# OpenSoundAnalog.net
KiCad netlist of a schematic drawn in EAGLE
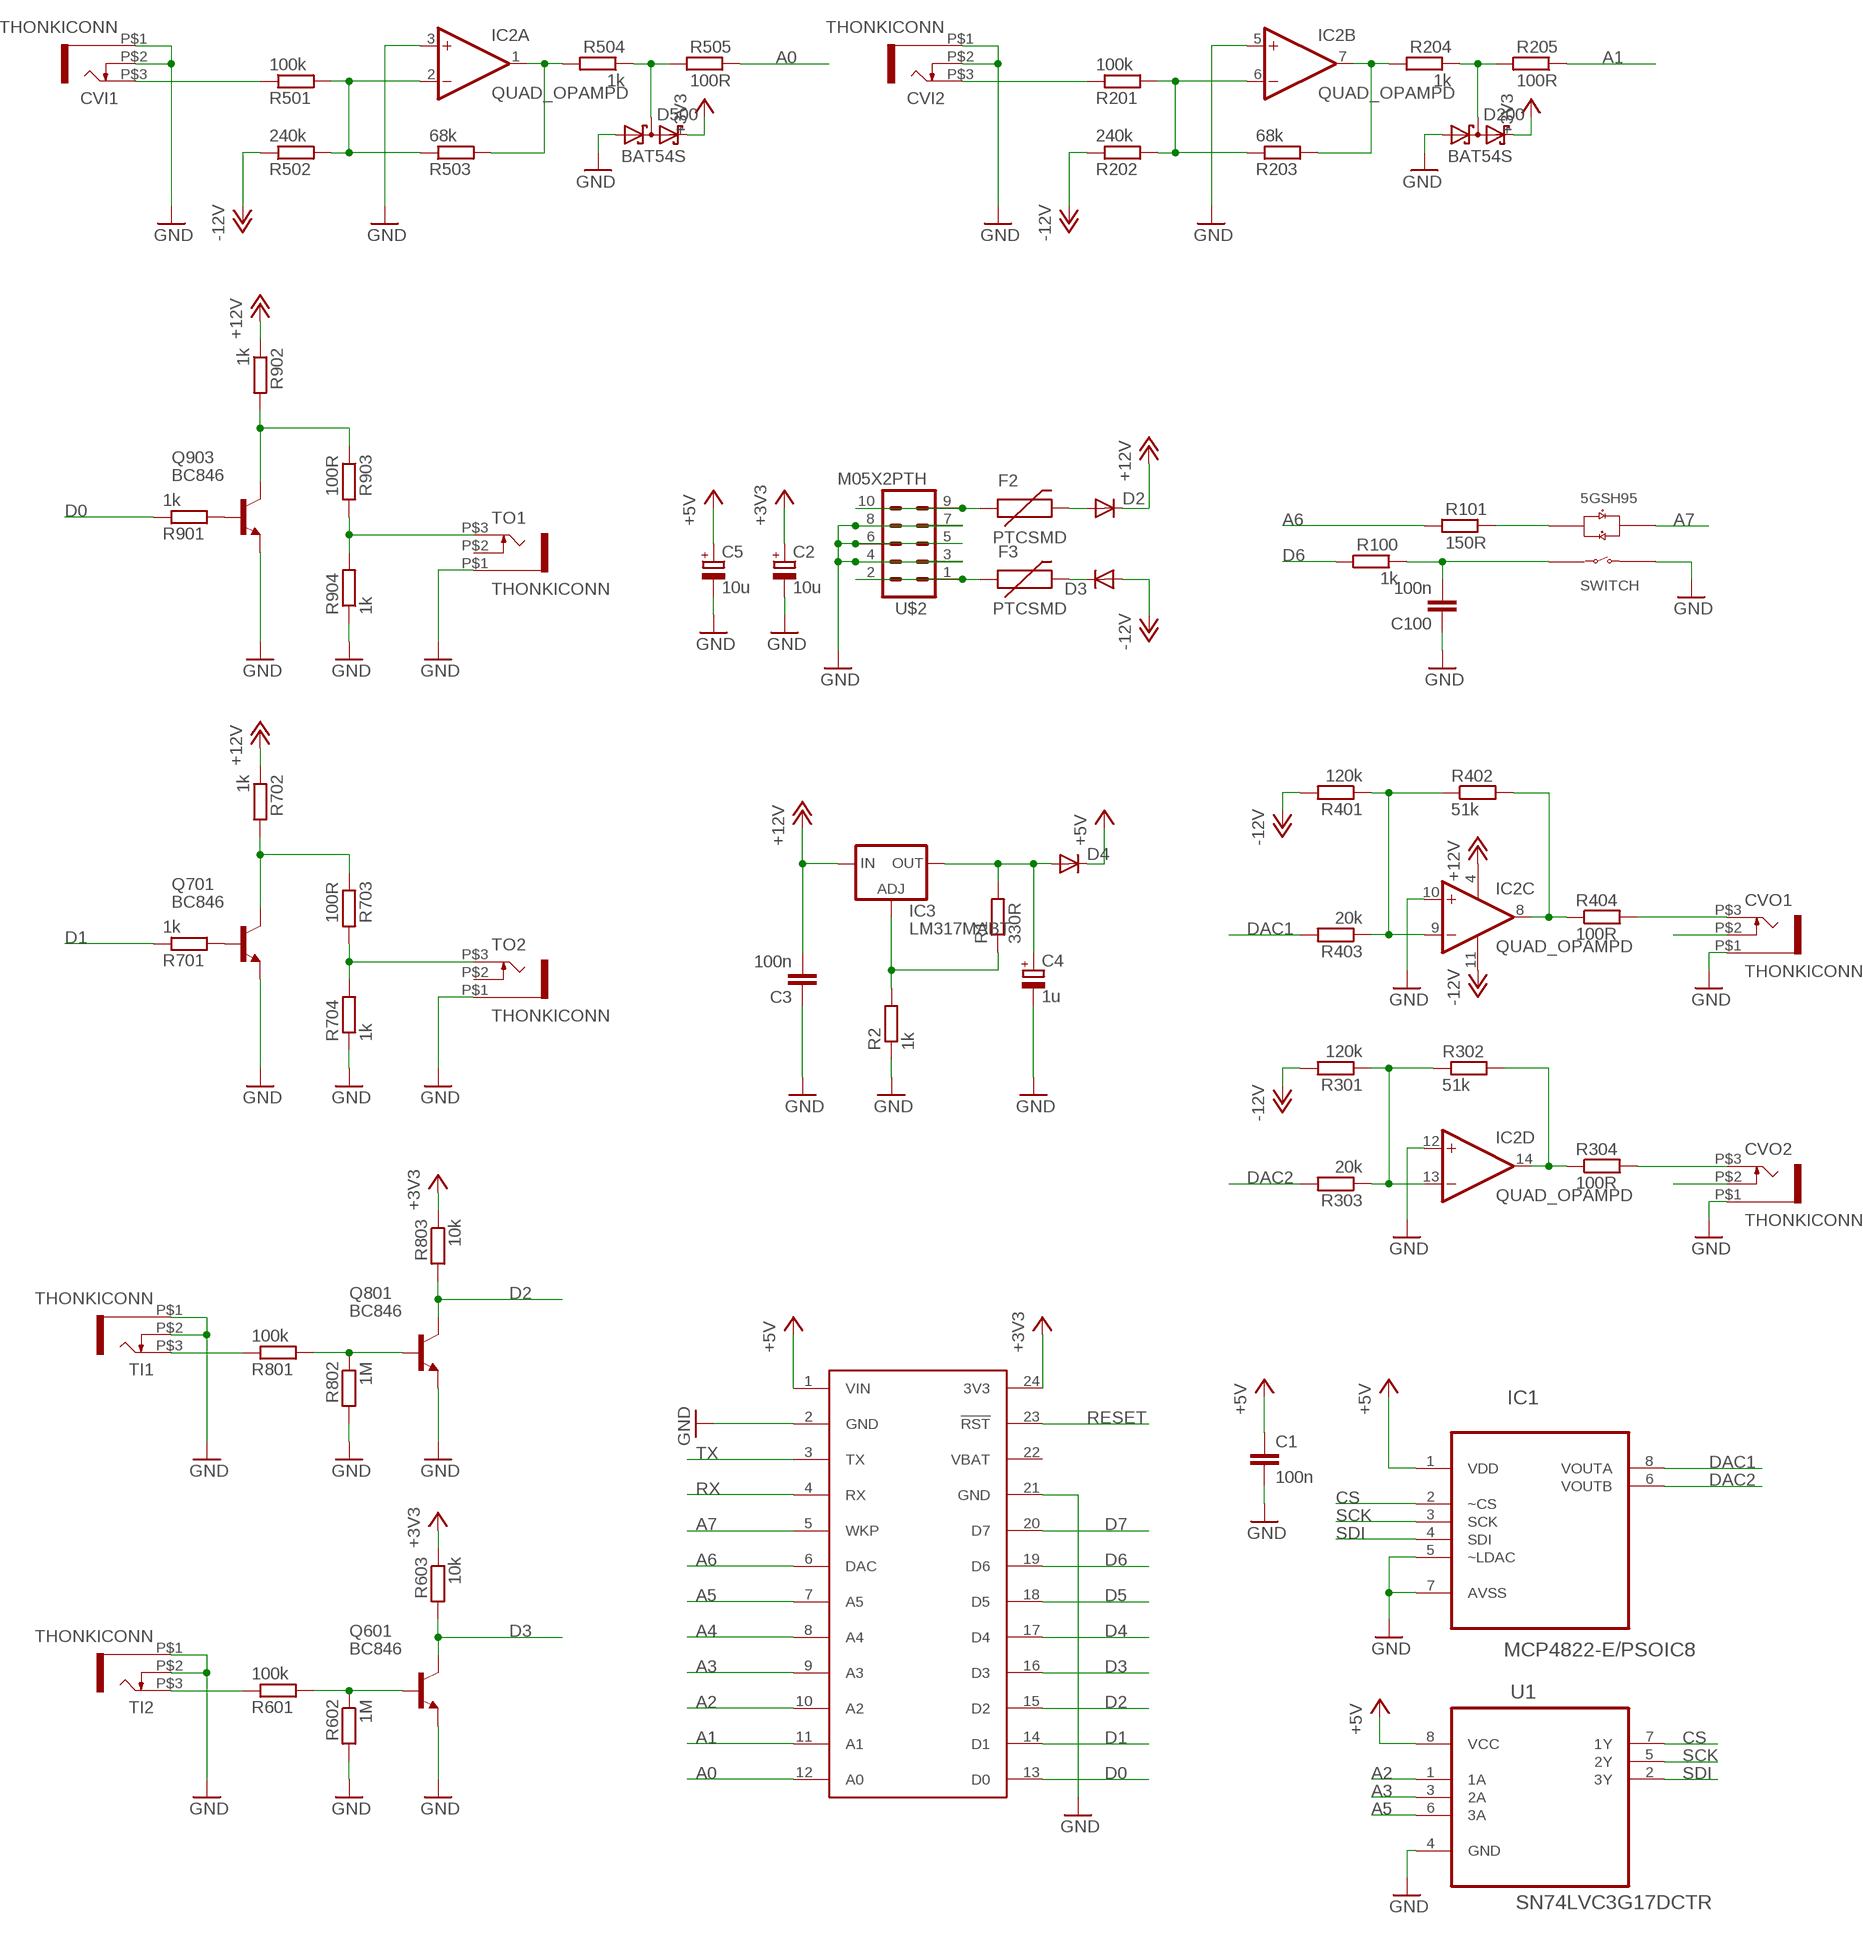
[diagram p0: schematic, sheet 1]

(export (version "E")
  (design (tool "Eeschema 10.0.6"))
  (components
    (comp (ref "C1")
      (value "100n")
      (footprint "eagle-import:C0603")
      (libsource (lib "eagle-import") (part "resistor_C-EUC0603"))
    )
    (comp (ref "C2")
      (value "10u")
      (footprint "eagle-import:SANYO-OSCON_SMD_A5")
      (libsource (lib "eagle-import") (part "CPOL-EUSANYO_SMD_A5"))
    )
    (comp (ref "C3")
      (value "100n")
      (footprint "eagle-import:C0603")
      (libsource (lib "eagle-import") (part "C-EUC0603"))
    )
    (comp (ref "C4")
      (value "1u")
      (footprint "eagle-import:SANYO-OSCON_SMD_A5")
      (libsource (lib "eagle-import") (part "CPOL-EUSANYO_SMD_A5"))
    )
    (comp (ref "C5")
      (value "10u")
      (footprint "eagle-import:SANYO-OSCON_SMD_A5")
      (libsource (lib "eagle-import") (part "CPOL-EUSANYO_SMD_A5"))
    )
    (comp (ref "C100")
      (value "100n")
      (footprint "eagle-import:C0603")
      (libsource (lib "eagle-import") (part "C-EUC0603"))
    )
    (comp (ref "CVI1")
      (value "THONKICONN")
      (footprint "eagle-import:THONKICONN")
      (libsource (lib "eagle-import") (part "THONKICONN"))
    )
    (comp (ref "CVI2")
      (value "THONKICONN")
      (footprint "eagle-import:THONKICONN")
      (libsource (lib "eagle-import") (part "THONKICONN"))
    )
    (comp (ref "CVO1")
      (value "THONKICONN")
      (footprint "eagle-import:THONKICONN")
      (libsource (lib "eagle-import") (part "THONKICONN"))
    )
    (comp (ref "CVO2")
      (value "THONKICONN")
      (footprint "eagle-import:THONKICONN")
      (libsource (lib "eagle-import") (part "THONKICONN"))
    )
    (comp (ref "D2")
      (value "DIODESMA")
      (footprint "eagle-import:SMA-DIODE")
      (libsource (lib "eagle-import") (part "DIODESMA"))
    )
    (comp (ref "D3")
      (value "DIODESMA")
      (footprint "eagle-import:SMA-DIODE")
      (libsource (lib "eagle-import") (part "DIODESMA"))
    )
    (comp (ref "D4")
      (value "DIODESMA")
      (footprint "eagle-import:SMA-DIODE")
      (libsource (lib "eagle-import") (part "DIODESMA"))
    )
    (comp (ref "D200")
      (value "BAT54S")
      (footprint "eagle-import:SOT23")
      (libsource (lib "eagle-import") (part "BAT54S"))
    )
    (comp (ref "D500")
      (value "BAT54S")
      (footprint "eagle-import:SOT23")
      (libsource (lib "eagle-import") (part "BAT54S"))
    )
    (comp (ref "F2")
      (value "PTCSMD")
      (footprint "eagle-import:PTC-1206")
      (libsource (lib "eagle-import") (part "PTCSMD"))
    )
    (comp (ref "F3")
      (value "PTCSMD")
      (footprint "eagle-import:PTC-1206")
      (libsource (lib "eagle-import") (part "PTCSMD"))
    )
    (comp (ref "IC1")
      (value "MCP4822-E/PSOIC8")
      (footprint "eagle-import:SOIC8")
      (libsource (lib "eagle-import") (part "MCP4822-E/PSOIC8"))
    )
    (comp (ref "IC2")
      (value "QUAD_OPAMPD")
      (footprint "eagle-import:SO14")
      (libsource (lib "eagle-import") (part "QUAD_OPAMPD"))
    )
    (comp (ref "IC3")
      (value "LM317MABT")
      (footprint "eagle-import:TO220L1")
      (libsource (lib "eagle-import") (part "LM317?MABT"))
    )
    (comp (ref "Q601")
      (value "BC846")
      (footprint "eagle-import:SOT23")
      (libsource (lib "eagle-import") (part "BC846"))
    )
    (comp (ref "Q701")
      (value "BC846")
      (footprint "eagle-import:SOT23")
      (libsource (lib "eagle-import") (part "BC846"))
    )
    (comp (ref "Q801")
      (value "BC846")
      (footprint "eagle-import:SOT23")
      (libsource (lib "eagle-import") (part "BC846"))
    )
    (comp (ref "Q903")
      (value "BC846")
      (footprint "eagle-import:SOT23")
      (libsource (lib "eagle-import") (part "BC846"))
    )
    (comp (ref "R1")
      (value "330R")
      (footprint "eagle-import:0603")
      (libsource (lib "eagle-import") (part "R-EU_0603"))
    )
    (comp (ref "R2")
      (value "1k")
      (footprint "eagle-import:0603")
      (libsource (lib "eagle-import") (part "R-EU_0603"))
    )
    (comp (ref "R100")
      (value "1k")
      (footprint "eagle-import:0603")
      (libsource (lib "eagle-import") (part "R-EU_0603"))
    )
    (comp (ref "R101")
      (value "150R")
      (footprint "eagle-import:0603")
      (libsource (lib "eagle-import") (part "R-EU_0603"))
    )
    (comp (ref "R201")
      (value "100k")
      (footprint "eagle-import:0603")
      (libsource (lib "eagle-import") (part "R-EU_0603"))
    )
    (comp (ref "R202")
      (value "240k")
      (footprint "eagle-import:0603")
      (libsource (lib "eagle-import") (part "R-EU_0603"))
    )
    (comp (ref "R203")
      (value "68k")
      (footprint "eagle-import:0603")
      (libsource (lib "eagle-import") (part "R-EU_0603"))
    )
    (comp (ref "R204")
      (value "1k")
      (footprint "eagle-import:0603")
      (libsource (lib "eagle-import") (part "R-EU_0603"))
    )
    (comp (ref "R205")
      (value "100R")
      (footprint "eagle-import:0603")
      (libsource (lib "eagle-import") (part "R-EU_0603"))
    )
    (comp (ref "R301")
      (value "120k")
      (footprint "eagle-import:0603")
      (libsource (lib "eagle-import") (part "R-EU_0603"))
    )
    (comp (ref "R302")
      (value "51k")
      (footprint "eagle-import:0603")
      (libsource (lib "eagle-import") (part "R-EU_0603"))
    )
    (comp (ref "R303")
      (value "20k")
      (footprint "eagle-import:0603")
      (libsource (lib "eagle-import") (part "R-EU_0603"))
    )
    (comp (ref "R304")
      (value "100R")
      (footprint "eagle-import:0603")
      (libsource (lib "eagle-import") (part "R-EU_0603"))
    )
    (comp (ref "R401")
      (value "120k")
      (footprint "eagle-import:0603")
      (libsource (lib "eagle-import") (part "R-EU_0603"))
    )
    (comp (ref "R402")
      (value "51k")
      (footprint "eagle-import:0603")
      (libsource (lib "eagle-import") (part "R-EU_0603"))
    )
    (comp (ref "R403")
      (value "20k")
      (footprint "eagle-import:0603")
      (libsource (lib "eagle-import") (part "R-EU_0603"))
    )
    (comp (ref "R404")
      (value "100R")
      (footprint "eagle-import:0603")
      (libsource (lib "eagle-import") (part "R-EU_0603"))
    )
    (comp (ref "R501")
      (value "100k")
      (footprint "eagle-import:0603")
      (libsource (lib "eagle-import") (part "R-EU_0603"))
    )
    (comp (ref "R502")
      (value "240k")
      (footprint "eagle-import:0603")
      (libsource (lib "eagle-import") (part "R-EU_0603"))
    )
    (comp (ref "R503")
      (value "68k")
      (footprint "eagle-import:0603")
      (libsource (lib "eagle-import") (part "R-EU_0603"))
    )
    (comp (ref "R504")
      (value "1k")
      (footprint "eagle-import:0603")
      (libsource (lib "eagle-import") (part "R-EU_0603"))
    )
    (comp (ref "R505")
      (value "100R")
      (footprint "eagle-import:0603")
      (libsource (lib "eagle-import") (part "R-EU_0603"))
    )
    (comp (ref "R601")
      (value "100k")
      (footprint "eagle-import:0603")
      (libsource (lib "eagle-import") (part "R-EU_0603"))
    )
    (comp (ref "R602")
      (value "1M")
      (footprint "eagle-import:0603")
      (libsource (lib "eagle-import") (part "R-EU_0603"))
    )
    (comp (ref "R603")
      (value "10k")
      (footprint "eagle-import:0603")
      (libsource (lib "eagle-import") (part "R-EU_0603"))
    )
    (comp (ref "R701")
      (value "1k")
      (footprint "eagle-import:0603")
      (libsource (lib "eagle-import") (part "R-EU_0603"))
    )
    (comp (ref "R702")
      (value "1k")
      (footprint "eagle-import:0603")
      (libsource (lib "eagle-import") (part "R-EU_0603"))
    )
    (comp (ref "R703")
      (value "100R")
      (footprint "eagle-import:0603")
      (libsource (lib "eagle-import") (part "R-EU_0603"))
    )
    (comp (ref "R704")
      (value "1k")
      (footprint "eagle-import:0603")
      (libsource (lib "eagle-import") (part "R-EU_0603"))
    )
    (comp (ref "R801")
      (value "100k")
      (footprint "eagle-import:0603")
      (libsource (lib "eagle-import") (part "R-EU_0603"))
    )
    (comp (ref "R802")
      (value "1M")
      (footprint "eagle-import:0603")
      (libsource (lib "eagle-import") (part "R-EU_0603"))
    )
    (comp (ref "R803")
      (value "10k")
      (footprint "eagle-import:0603")
      (libsource (lib "eagle-import") (part "R-EU_0603"))
    )
    (comp (ref "R901")
      (value "1k")
      (footprint "eagle-import:0603")
      (libsource (lib "eagle-import") (part "R-EU_0603"))
    )
    (comp (ref "R902")
      (value "1k")
      (footprint "eagle-import:0603")
      (libsource (lib "eagle-import") (part "R-EU_0603"))
    )
    (comp (ref "R903")
      (value "100R")
      (footprint "eagle-import:0603")
      (libsource (lib "eagle-import") (part "R-EU_0603"))
    )
    (comp (ref "R904")
      (value "1k")
      (footprint "eagle-import:0603")
      (libsource (lib "eagle-import") (part "R-EU_0603"))
    )
    (comp (ref "SPARK")
      (value "SPARK_CORE")
      (footprint "eagle-import:SPARK_CORE")
      (libsource (lib "eagle-import") (part "SPARK_CORECORE"))
    )
    (comp (ref "TI1")
      (value "THONKICONN")
      (footprint "eagle-import:THONKICONN")
      (libsource (lib "eagle-import") (part "THONKICONN"))
    )
    (comp (ref "TI2")
      (value "THONKICONN")
      (footprint "eagle-import:THONKICONN")
      (libsource (lib "eagle-import") (part "THONKICONN"))
    )
    (comp (ref "TO1")
      (value "THONKICONN")
      (footprint "eagle-import:THONKICONN")
      (libsource (lib "eagle-import") (part "THONKICONN"))
    )
    (comp (ref "TO2")
      (value "THONKICONN")
      (footprint "eagle-import:THONKICONN")
      (libsource (lib "eagle-import") (part "THONKICONN"))
    )
    (comp (ref "U$1")
      (value "5GTH9")
      (footprint "eagle-import:5GTH9")
      (libsource (lib "eagle-import") (part "5GTH9"))
    )
    (comp (ref "U$2")
      (value "M05X2PTH")
      (footprint "eagle-import:AVR_ICSP")
      (libsource (lib "eagle-import") (part "M05X2PTH"))
    )
    (comp (ref "U1")
      (value "SN74LVC3G17DCTR")
      (footprint "eagle-import:SOP65P400X130-8N")
      (libsource (lib "eagle-import") (part "SN74LVC3G17DCTR"))
    )
  )
  (nets
    (net (code "1") (name "+3V3") (class "Default")
      (node (ref "C2") (pin "+") (pinfunction "+_+") (pintype "passive"))
      (node (ref "D200") (pin "2") (pinfunction "C2_2") (pintype "passive"))
      (node (ref "D500") (pin "2") (pinfunction "C2_2") (pintype "passive"))
      (node (ref "R603") (pin "1") (pinfunction "1_1") (pintype "passive"))
      (node (ref "R803") (pin "1") (pinfunction "1_1") (pintype "passive"))
      (node (ref "SPARK") (pin "24") (pinfunction "3V3_24") (pintype "power_in"))
    )
    (net (code "2") (name "+5V") (class "Default")
      (node (ref "C1") (pin "1") (pinfunction "1_1") (pintype "passive"))
      (node (ref "C5") (pin "+") (pinfunction "+_+") (pintype "passive"))
      (node (ref "D4") (pin "C") (pinfunction "C_C") (pintype "passive"))
      (node (ref "IC1") (pin "1") (pinfunction "VDD_1") (pintype "power_in"))
      (node (ref "SPARK") (pin "1") (pinfunction "VIN_1") (pintype "power_in"))
      (node (ref "U1") (pin "8") (pinfunction "VCC_8") (pintype "power_in"))
    )
    (net (code "3") (name "+12V") (class "Default")
      (node (ref "C3") (pin "2") (pinfunction "2_2") (pintype "passive"))
      (node (ref "D2") (pin "C") (pinfunction "C_C") (pintype "passive"))
      (node (ref "IC2") (pin "4") (pinfunction "V+_4") (pintype "power_in"))
      (node (ref "IC3") (pin "3") (pinfunction "IN_3") (pintype "input"))
      (node (ref "R702") (pin "1") (pinfunction "1_1") (pintype "passive"))
      (node (ref "R902") (pin "1") (pinfunction "1_1") (pintype "passive"))
    )
    (net (code "4") (name "-12V") (class "Default")
      (node (ref "D3") (pin "A") (pinfunction "A_A") (pintype "passive"))
      (node (ref "IC2") (pin "11") (pinfunction "V-_11") (pintype "power_in"))
      (node (ref "R202") (pin "1") (pinfunction "1_1") (pintype "passive"))
      (node (ref "R301") (pin "2") (pinfunction "2_2") (pintype "passive"))
      (node (ref "R401") (pin "2") (pinfunction "2_2") (pintype "passive"))
      (node (ref "R502") (pin "1") (pinfunction "1_1") (pintype "passive"))
    )
    (net (code "5") (name "/A0") (class "Default")
      (node (ref "R505") (pin "1") (pinfunction "1_1") (pintype "passive"))
      (node (ref "SPARK") (pin "12") (pinfunction "A0_12") (pintype "bidirectional"))
    )
    (net (code "6") (name "/A1") (class "Default")
      (node (ref "R205") (pin "1") (pinfunction "1_1") (pintype "passive"))
      (node (ref "SPARK") (pin "11") (pinfunction "A1_11") (pintype "bidirectional"))
    )
    (net (code "7") (name "/A2") (class "Default")
      (node (ref "SPARK") (pin "10") (pinfunction "A2_10") (pintype "bidirectional"))
      (node (ref "U1") (pin "1") (pinfunction "1A_1") (pintype "input"))
    )
    (net (code "8") (name "/A3") (class "Default")
      (node (ref "SPARK") (pin "9") (pinfunction "A3_9") (pintype "bidirectional"))
      (node (ref "U1") (pin "3") (pinfunction "2A_3") (pintype "input"))
    )
    (net (code "9") (name "/A4") (class "Default")
      (node (ref "SPARK") (pin "8") (pinfunction "A4_8") (pintype "bidirectional"))
    )
    (net (code "10") (name "/A5") (class "Default")
      (node (ref "SPARK") (pin "7") (pinfunction "A5_7") (pintype "bidirectional"))
      (node (ref "U1") (pin "6") (pinfunction "3A_6") (pintype "input"))
    )
    (net (code "11") (name "/A6") (class "Default")
      (node (ref "R101") (pin "2") (pinfunction "2_2") (pintype "passive"))
      (node (ref "SPARK") (pin "6") (pinfunction "DAC_6") (pintype "bidirectional"))
    )
    (net (code "12") (name "/A7") (class "Default")
      (node (ref "SPARK") (pin "5") (pinfunction "WKP_5") (pintype "bidirectional"))
      (node (ref "U$1") (pin "+3") (pinfunction "LED_R+_+3") (pintype "input"))
    )
    (net (code "13") (name "/CS") (class "Default")
      (node (ref "IC1") (pin "2") (pinfunction "~{CS}_2") (pintype "input"))
      (node (ref "U1") (pin "7") (pinfunction "1Y_7") (pintype "output"))
    )
    (net (code "14") (name "/D0") (class "Default")
      (node (ref "R901") (pin "1") (pinfunction "1_1") (pintype "passive"))
      (node (ref "SPARK") (pin "13") (pinfunction "D0_13") (pintype "bidirectional"))
    )
    (net (code "15") (name "/D1") (class "Default")
      (node (ref "R701") (pin "1") (pinfunction "1_1") (pintype "passive"))
      (node (ref "SPARK") (pin "14") (pinfunction "D1_14") (pintype "bidirectional"))
    )
    (net (code "16") (name "/D2") (class "Default")
      (node (ref "Q801") (pin "3") (pinfunction "C_3") (pintype "passive"))
      (node (ref "R803") (pin "2") (pinfunction "2_2") (pintype "passive"))
      (node (ref "SPARK") (pin "15") (pinfunction "D2_15") (pintype "bidirectional"))
    )
    (net (code "17") (name "/D3") (class "Default")
      (node (ref "Q601") (pin "3") (pinfunction "C_3") (pintype "passive"))
      (node (ref "R603") (pin "2") (pinfunction "2_2") (pintype "passive"))
      (node (ref "SPARK") (pin "16") (pinfunction "D3_16") (pintype "bidirectional"))
    )
    (net (code "18") (name "/D4") (class "Default")
      (node (ref "SPARK") (pin "17") (pinfunction "D4_17") (pintype "bidirectional"))
    )
    (net (code "19") (name "/D5") (class "Default")
      (node (ref "SPARK") (pin "18") (pinfunction "D5_18") (pintype "bidirectional"))
    )
    (net (code "20") (name "/D6") (class "Default")
      (node (ref "R100") (pin "2") (pinfunction "2_2") (pintype "passive"))
      (node (ref "SPARK") (pin "19") (pinfunction "D6_19") (pintype "bidirectional"))
    )
    (net (code "21") (name "/D7") (class "Default")
      (node (ref "SPARK") (pin "20") (pinfunction "D7_20") (pintype "bidirectional"))
    )
    (net (code "22") (name "/DAC1") (class "Default")
      (node (ref "IC1") (pin "8") (pinfunction "VOUTA_8") (pintype "output"))
      (node (ref "R403") (pin "2") (pinfunction "2_2") (pintype "passive"))
    )
    (net (code "23") (name "/DAC2") (class "Default")
      (node (ref "IC1") (pin "6") (pinfunction "VOUTB_6") (pintype "output"))
      (node (ref "R303") (pin "2") (pinfunction "2_2") (pintype "passive"))
    )
    (net (code "24") (name "/RESET") (class "Default")
      (node (ref "SPARK") (pin "23") (pinfunction "~{RST}_23") (pintype "bidirectional"))
    )
    (net (code "25") (name "/RX") (class "Default")
      (node (ref "SPARK") (pin "4") (pinfunction "RX_4") (pintype "bidirectional"))
    )
    (net (code "26") (name "/SCK") (class "Default")
      (node (ref "IC1") (pin "3") (pinfunction "SCK_3") (pintype "input"))
      (node (ref "U1") (pin "5") (pinfunction "2Y_5") (pintype "output"))
    )
    (net (code "27") (name "/SDI") (class "Default")
      (node (ref "IC1") (pin "4") (pinfunction "SDI_4") (pintype "input"))
      (node (ref "U1") (pin "2") (pinfunction "3Y_2") (pintype "output"))
    )
    (net (code "28") (name "/TX") (class "Default")
      (node (ref "SPARK") (pin "3") (pinfunction "TX_3") (pintype "bidirectional"))
    )
    (net (code "29") (name "/VBAT") (class "Default")
      (node (ref "SPARK") (pin "22") (pinfunction "VBAT_22") (pintype "power_in"))
    )
    (net (code "30") (name "GND") (class "Default")
      (node (ref "C1") (pin "2") (pinfunction "2_2") (pintype "passive"))
      (node (ref "C100") (pin "1") (pinfunction "1_1") (pintype "passive"))
      (node (ref "C2") (pin "-") (pinfunction "-_-") (pintype "passive"))
      (node (ref "C3") (pin "1") (pinfunction "1_1") (pintype "passive"))
      (node (ref "C4") (pin "-") (pinfunction "-_-") (pintype "passive"))
      (node (ref "C5") (pin "-") (pinfunction "-_-") (pintype "passive"))
      (node (ref "CVI1") (pin "P$1") (pinfunction "5_P$1") (pintype "passive"))
      (node (ref "CVI1") (pin "P$2") (pinfunction "4_P$2") (pintype "passive"))
      (node (ref "CVI2") (pin "P$1") (pinfunction "5_P$1") (pintype "passive"))
      (node (ref "CVI2") (pin "P$2") (pinfunction "4_P$2") (pintype "passive"))
      (node (ref "CVO1") (pin "P$1") (pinfunction "5_P$1") (pintype "passive"))
      (node (ref "CVO2") (pin "P$1") (pinfunction "5_P$1") (pintype "passive"))
      (node (ref "D200") (pin "1") (pinfunction "A1_1") (pintype "passive"))
      (node (ref "D500") (pin "1") (pinfunction "A1_1") (pintype "passive"))
      (node (ref "IC1") (pin "5") (pinfunction "~{LDAC}_5") (pintype "input"))
      (node (ref "IC1") (pin "7") (pinfunction "AVSS_7") (pintype "passive"))
      (node (ref "IC2") (pin "10") (pinfunction "+IN_10") (pintype "input"))
      (node (ref "IC2") (pin "12") (pinfunction "+IN_12") (pintype "input"))
      (node (ref "IC2") (pin "3") (pinfunction "+IN_3") (pintype "input"))
      (node (ref "IC2") (pin "5") (pinfunction "+IN_5") (pintype "input"))
      (node (ref "Q601") (pin "2") (pinfunction "E_2") (pintype "passive"))
      (node (ref "Q701") (pin "2") (pinfunction "E_2") (pintype "passive"))
      (node (ref "Q801") (pin "2") (pinfunction "E_2") (pintype "passive"))
      (node (ref "Q903") (pin "2") (pinfunction "E_2") (pintype "passive"))
      (node (ref "R2") (pin "1") (pinfunction "1_1") (pintype "passive"))
      (node (ref "R602") (pin "2") (pinfunction "2_2") (pintype "passive"))
      (node (ref "R704") (pin "1") (pinfunction "1_1") (pintype "passive"))
      (node (ref "R802") (pin "2") (pinfunction "2_2") (pintype "passive"))
      (node (ref "R904") (pin "1") (pinfunction "1_1") (pintype "passive"))
      (node (ref "SPARK") (pin "2") (pinfunction "GND_2") (pintype "power_in"))
      (node (ref "SPARK") (pin "21") (pinfunction "GND_21") (pintype "power_in"))
      (node (ref "TI1") (pin "P$1") (pinfunction "5_P$1") (pintype "passive"))
      (node (ref "TI1") (pin "P$2") (pinfunction "4_P$2") (pintype "passive"))
      (node (ref "TI2") (pin "P$1") (pinfunction "5_P$1") (pintype "passive"))
      (node (ref "TI2") (pin "P$2") (pinfunction "4_P$2") (pintype "passive"))
      (node (ref "TO1") (pin "P$1") (pinfunction "5_P$1") (pintype "passive"))
      (node (ref "TO2") (pin "P$1") (pinfunction "5_P$1") (pintype "passive"))
      (node (ref "U$1") (pin "1") (pinfunction "SWITCH_B_1") (pintype "power_in"))
      (node (ref "U$2") (pin "3") (pinfunction "3_3") (pintype "passive"))
      (node (ref "U$2") (pin "4") (pinfunction "4_4") (pintype "passive"))
      (node (ref "U$2") (pin "5") (pinfunction "5_5") (pintype "passive"))
      (node (ref "U$2") (pin "6") (pinfunction "6_6") (pintype "passive"))
      (node (ref "U$2") (pin "7") (pinfunction "7_7") (pintype "passive"))
      (node (ref "U$2") (pin "8") (pinfunction "8_8") (pintype "passive"))
      (node (ref "U1") (pin "4") (pinfunction "GND_4") (pintype "passive"))
    )
    (net (code "31") (name "Net-(CVI1-3)") (class "Default")
      (node (ref "CVI1") (pin "P$3") (pinfunction "3_P$3") (pintype "passive"))
      (node (ref "R501") (pin "1") (pinfunction "1_1") (pintype "passive"))
    )
    (net (code "32") (name "Net-(CVI2-3)") (class "Default")
      (node (ref "CVI2") (pin "P$3") (pinfunction "3_P$3") (pintype "passive"))
      (node (ref "R201") (pin "1") (pinfunction "1_1") (pintype "passive"))
    )
    (net (code "33") (name "Net-(CVO1-3)") (class "Default")
      (node (ref "CVO1") (pin "P$3") (pinfunction "3_P$3") (pintype "passive"))
      (node (ref "R404") (pin "2") (pinfunction "2_2") (pintype "passive"))
    )
    (net (code "34") (name "Net-(CVO2-3)") (class "Default")
      (node (ref "CVO2") (pin "P$3") (pinfunction "3_P$3") (pintype "passive"))
      (node (ref "R304") (pin "2") (pinfunction "2_2") (pintype "passive"))
    )
    (net (code "35") (name "Net-(D2-PadA)") (class "Default")
      (node (ref "D2") (pin "A") (pinfunction "A_A") (pintype "passive"))
      (node (ref "F2") (pin "2") (pinfunction "2_2") (pintype "bidirectional"))
    )
    (net (code "36") (name "Net-(D3-PadC)") (class "Default")
      (node (ref "D3") (pin "C") (pinfunction "C_C") (pintype "passive"))
      (node (ref "F3") (pin "2") (pinfunction "2_2") (pintype "bidirectional"))
    )
    (net (code "37") (name "Net-(D200-C1A2)") (class "Default")
      (node (ref "D200") (pin "3") (pinfunction "C1A2_3") (pintype "passive"))
      (node (ref "R204") (pin "1") (pinfunction "1_1") (pintype "passive"))
      (node (ref "R205") (pin "2") (pinfunction "2_2") (pintype "passive"))
    )
    (net (code "38") (name "Net-(D500-C1A2)") (class "Default")
      (node (ref "D500") (pin "3") (pinfunction "C1A2_3") (pintype "passive"))
      (node (ref "R504") (pin "1") (pinfunction "1_1") (pintype "passive"))
      (node (ref "R505") (pin "2") (pinfunction "2_2") (pintype "passive"))
    )
    (net (code "39") (name "Net-(F2-Pad1)") (class "Default")
      (node (ref "F2") (pin "1") (pinfunction "1_1") (pintype "bidirectional"))
      (node (ref "U$2") (pin "10") (pinfunction "10_10") (pintype "passive"))
      (node (ref "U$2") (pin "9") (pinfunction "9_9") (pintype "passive"))
    )
    (net (code "40") (name "Net-(F3-Pad1)") (class "Default")
      (node (ref "F3") (pin "1") (pinfunction "1_1") (pintype "bidirectional"))
      (node (ref "U$2") (pin "1") (pinfunction "1_1") (pintype "passive"))
      (node (ref "U$2") (pin "2") (pinfunction "2_2") (pintype "passive"))
    )
    (net (code "41") (name "Net-(IC2A--IN)") (class "Default")
      (node (ref "IC2") (pin "2") (pinfunction "-IN_2") (pintype "input"))
      (node (ref "R501") (pin "2") (pinfunction "2_2") (pintype "passive"))
      (node (ref "R502") (pin "2") (pinfunction "2_2") (pintype "passive"))
      (node (ref "R503") (pin "1") (pinfunction "1_1") (pintype "passive"))
    )
    (net (code "42") (name "Net-(IC2A-OUT)") (class "Default")
      (node (ref "IC2") (pin "1") (pinfunction "OUT_1") (pintype "output"))
      (node (ref "R503") (pin "2") (pinfunction "2_2") (pintype "passive"))
      (node (ref "R504") (pin "2") (pinfunction "2_2") (pintype "passive"))
    )
    (net (code "43") (name "Net-(IC2B--IN)") (class "Default")
      (node (ref "IC2") (pin "6") (pinfunction "-IN_6") (pintype "input"))
      (node (ref "R201") (pin "2") (pinfunction "2_2") (pintype "passive"))
      (node (ref "R202") (pin "2") (pinfunction "2_2") (pintype "passive"))
      (node (ref "R203") (pin "1") (pinfunction "1_1") (pintype "passive"))
    )
    (net (code "44") (name "Net-(IC2B-OUT)") (class "Default")
      (node (ref "IC2") (pin "7") (pinfunction "OUT_7") (pintype "output"))
      (node (ref "R203") (pin "2") (pinfunction "2_2") (pintype "passive"))
      (node (ref "R204") (pin "2") (pinfunction "2_2") (pintype "passive"))
    )
    (net (code "45") (name "Net-(IC2C--IN)") (class "Default")
      (node (ref "IC2") (pin "9") (pinfunction "-IN_9") (pintype "input"))
      (node (ref "R401") (pin "1") (pinfunction "1_1") (pintype "passive"))
      (node (ref "R402") (pin "1") (pinfunction "1_1") (pintype "passive"))
      (node (ref "R403") (pin "1") (pinfunction "1_1") (pintype "passive"))
    )
    (net (code "46") (name "Net-(IC2C-OUT)") (class "Default")
      (node (ref "IC2") (pin "8") (pinfunction "OUT_8") (pintype "output"))
      (node (ref "R402") (pin "2") (pinfunction "2_2") (pintype "passive"))
      (node (ref "R404") (pin "1") (pinfunction "1_1") (pintype "passive"))
    )
    (net (code "47") (name "Net-(IC2D--IN)") (class "Default")
      (node (ref "IC2") (pin "13") (pinfunction "-IN_13") (pintype "input"))
      (node (ref "R301") (pin "1") (pinfunction "1_1") (pintype "passive"))
      (node (ref "R302") (pin "1") (pinfunction "1_1") (pintype "passive"))
      (node (ref "R303") (pin "1") (pinfunction "1_1") (pintype "passive"))
    )
    (net (code "48") (name "Net-(IC2D-OUT)") (class "Default")
      (node (ref "IC2") (pin "14") (pinfunction "OUT_14") (pintype "output"))
      (node (ref "R302") (pin "2") (pinfunction "2_2") (pintype "passive"))
      (node (ref "R304") (pin "1") (pinfunction "1_1") (pintype "passive"))
    )
    (net (code "49") (name "Net-(IC3-ADJ)") (class "Default")
      (node (ref "IC3") (pin "1") (pinfunction "ADJ_1") (pintype "input"))
      (node (ref "R1") (pin "1") (pinfunction "1_1") (pintype "passive"))
      (node (ref "R2") (pin "2") (pinfunction "2_2") (pintype "passive"))
    )
    (net (code "50") (name "Net-(IC3-OUT)") (class "Default")
      (node (ref "C4") (pin "+") (pinfunction "+_+") (pintype "passive"))
      (node (ref "D4") (pin "A") (pinfunction "A_A") (pintype "passive"))
      (node (ref "IC3") (pin "2") (pinfunction "OUT_2") (pintype "passive"))
      (node (ref "R1") (pin "2") (pinfunction "2_2") (pintype "passive"))
    )
    (net (code "51") (name "Net-(Q601-B)") (class "Default")
      (node (ref "Q601") (pin "1") (pinfunction "B_1") (pintype "passive"))
      (node (ref "R601") (pin "2") (pinfunction "2_2") (pintype "passive"))
      (node (ref "R602") (pin "1") (pinfunction "1_1") (pintype "passive"))
    )
    (net (code "52") (name "Net-(Q701-B)") (class "Default")
      (node (ref "Q701") (pin "1") (pinfunction "B_1") (pintype "passive"))
      (node (ref "R701") (pin "2") (pinfunction "2_2") (pintype "passive"))
    )
    (net (code "53") (name "Net-(Q701-C)") (class "Default")
      (node (ref "Q701") (pin "3") (pinfunction "C_3") (pintype "passive"))
      (node (ref "R702") (pin "2") (pinfunction "2_2") (pintype "passive"))
      (node (ref "R703") (pin "1") (pinfunction "1_1") (pintype "passive"))
    )
    (net (code "54") (name "Net-(Q801-B)") (class "Default")
      (node (ref "Q801") (pin "1") (pinfunction "B_1") (pintype "passive"))
      (node (ref "R801") (pin "2") (pinfunction "2_2") (pintype "passive"))
      (node (ref "R802") (pin "1") (pinfunction "1_1") (pintype "passive"))
    )
    (net (code "55") (name "Net-(Q903-B)") (class "Default")
      (node (ref "Q903") (pin "1") (pinfunction "B_1") (pintype "passive"))
      (node (ref "R901") (pin "2") (pinfunction "2_2") (pintype "passive"))
    )
    (net (code "56") (name "Net-(Q903-C)") (class "Default")
      (node (ref "Q903") (pin "3") (pinfunction "C_3") (pintype "passive"))
      (node (ref "R902") (pin "2") (pinfunction "2_2") (pintype "passive"))
      (node (ref "R903") (pin "1") (pinfunction "1_1") (pintype "passive"))
    )
    (net (code "57") (name "Net-(TI1-3)") (class "Default")
      (node (ref "R801") (pin "1") (pinfunction "1_1") (pintype "passive"))
      (node (ref "TI1") (pin "P$3") (pinfunction "3_P$3") (pintype "passive"))
    )
    (net (code "58") (name "Net-(TI2-3)") (class "Default")
      (node (ref "R601") (pin "1") (pinfunction "1_1") (pintype "passive"))
      (node (ref "TI2") (pin "P$3") (pinfunction "3_P$3") (pintype "passive"))
    )
    (net (code "59") (name "Net-(TO1-3)") (class "Default")
      (node (ref "R903") (pin "2") (pinfunction "2_2") (pintype "passive"))
      (node (ref "R904") (pin "2") (pinfunction "2_2") (pintype "passive"))
      (node (ref "TO1") (pin "P$3") (pinfunction "3_P$3") (pintype "passive"))
    )
    (net (code "60") (name "Net-(TO2-3)") (class "Default")
      (node (ref "R703") (pin "2") (pinfunction "2_2") (pintype "passive"))
      (node (ref "R704") (pin "2") (pinfunction "2_2") (pintype "passive"))
      (node (ref "TO2") (pin "P$3") (pinfunction "3_P$3") (pintype "passive"))
    )
    (net (code "61") (name "Net-(U$1-LED_G+)") (class "Default")
      (node (ref "R101") (pin "1") (pinfunction "1_1") (pintype "passive"))
      (node (ref "U$1") (pin "-2") (pinfunction "LED_G+_-2") (pintype "input"))
    )
    (net (code "62") (name "Net-(U$1-SWITCH_A)") (class "Default")
      (node (ref "C100") (pin "2") (pinfunction "2_2") (pintype "passive"))
      (node (ref "R100") (pin "1") (pinfunction "1_1") (pintype "passive"))
      (node (ref "U$1") (pin "4") (pinfunction "SWITCH_A_4") (pintype "power_in"))
    )
    (net (code "63") (name "unconnected-(CVO1-4-PadP$2)") (class "Default")
      (node (ref "CVO1") (pin "P$2") (pinfunction "4_P$2") (pintype "passive"))
    )
    (net (code "64") (name "unconnected-(CVO2-4-PadP$2)") (class "Default")
      (node (ref "CVO2") (pin "P$2") (pinfunction "4_P$2") (pintype "passive"))
    )
    (net (code "65") (name "unconnected-(TO1-4-PadP$2)") (class "Default")
      (node (ref "TO1") (pin "P$2") (pinfunction "4_P$2") (pintype "passive"))
    )
    (net (code "66") (name "unconnected-(TO2-4-PadP$2)") (class "Default")
      (node (ref "TO2") (pin "P$2") (pinfunction "4_P$2") (pintype "passive"))
    )
  )
)
